# SCH_D69-600V_supply_2024-10-20.net
KiCad netlist of a schematic drawn in EasyEDA
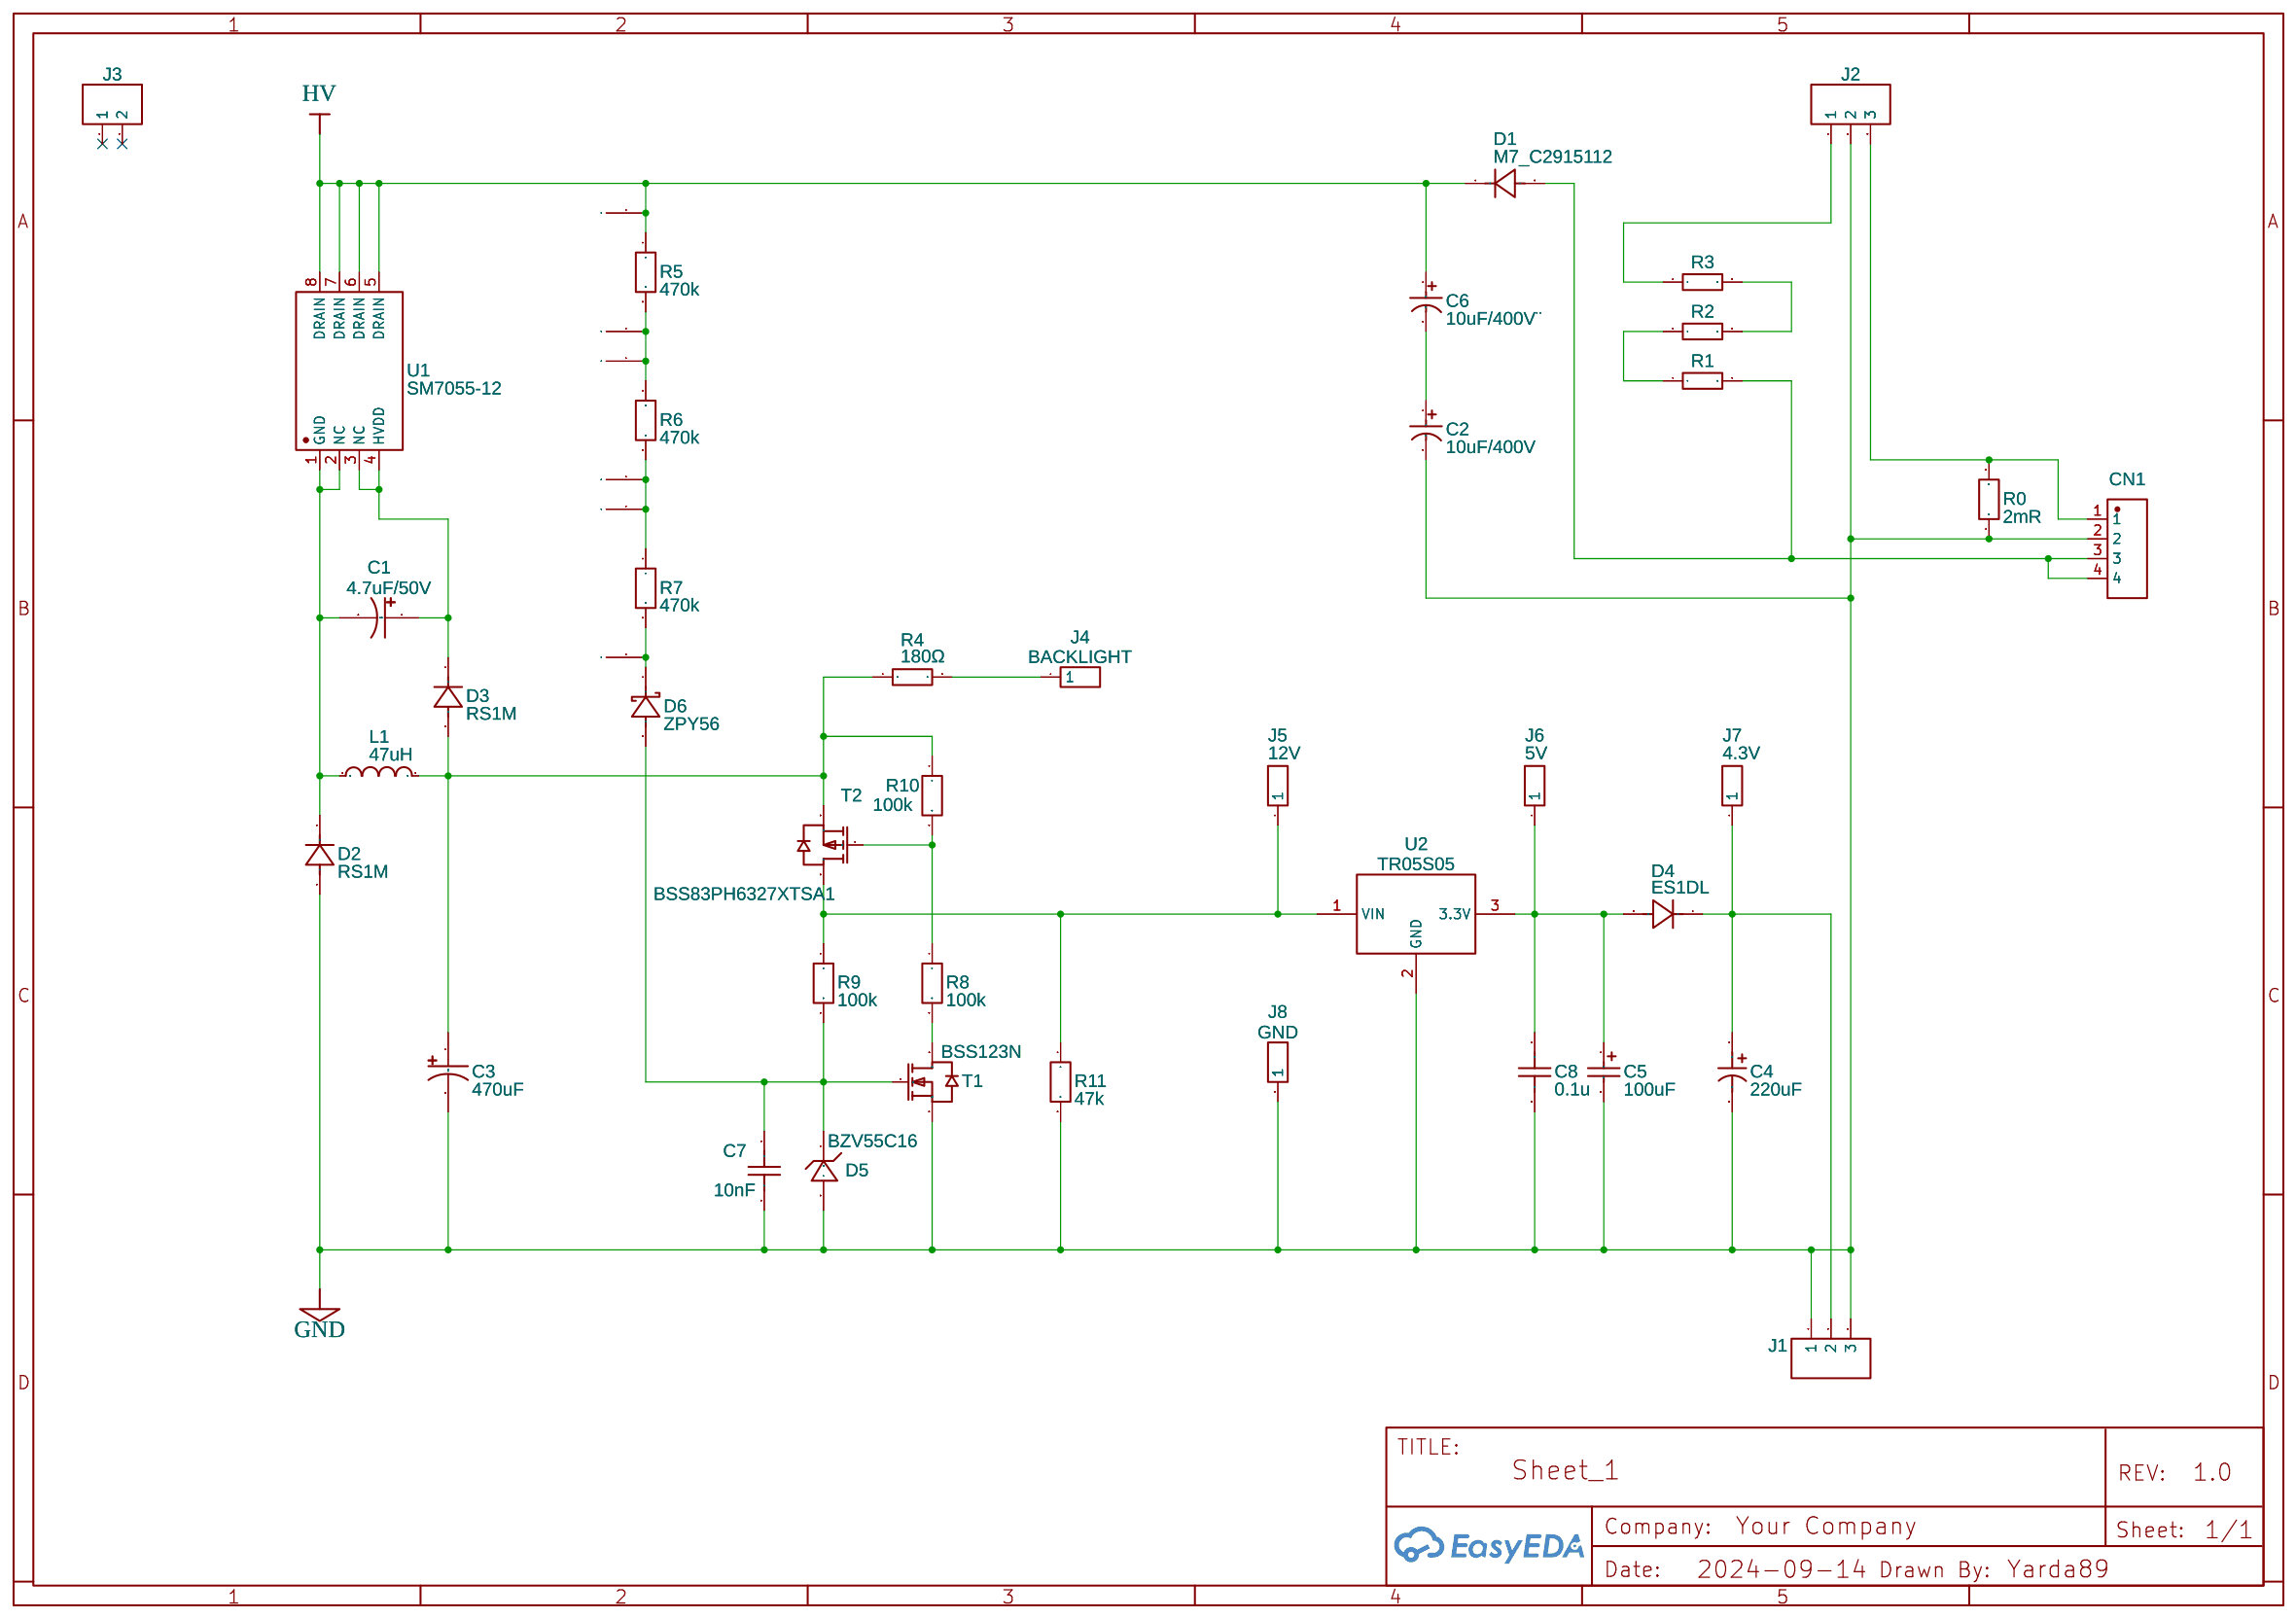
[diagram p0: schematic sheet]

(export (version "E")
  (design (tool "Eeschema 10.0.6"))
  (components
    (comp (ref "C1")
      (value "4.7uF/50V")
      (fields (field (name "Manufacturer Part") "EEUFR1H4R7") (field (name "Manufacturer") "PANASONIC(松下)"))
      (libsource (lib "") (part "EEUFR1H4R7"))
    )
    (comp (ref "C2")
      (value "10uF/400V")
      (fields (field (name "Manufacturer Part") "UCS2G100MPD") (field (name "Manufacturer") "Nichicon(尼吉康)"))
      (libsource (lib "") (part "UCS2G100MPD"))
    )
    (comp (ref "C3")
      (value "470uF")
      (fields (field (name "Manufacturer Part") "EEUFR1E471Y") (field (name "Manufacturer") "PANASONIC(松下)"))
      (libsource (lib "") (part "EEUFR1E471Y"))
    )
    (comp (ref "C4")
      (value "220uF")
      (fields (field (name "Manufacturer Part") "ECA1CM221") (field (name "Manufacturer") "PANASONIC(松下)"))
      (libsource (lib "") (part "ECA1CM221"))
    )
    (comp (ref "C5")
      (value "100uF")
      (fields (field (name "Manufacturer Part") "TAJD107M016RNJ") (field (name "Manufacturer") "Kyocera AVX"))
      (libsource (lib "") (part "TAJD107M016RNJ"))
    )
    (comp (ref "C6")
      (value "10uF/400V¨")
      (fields (field (name "Manufacturer Part") "UCS2G100MPD") (field (name "Manufacturer") "Nichicon(尼吉康)"))
      (libsource (lib "") (part "UCS2G100MPD"))
    )
    (comp (ref "C7")
      (value "10nF")
      (fields
        (field (name "Manufacturer Part") "CC1H103ZA1ED3F4D1100")
        (field (name "Manufacturer") "Dersonic(德尔创)")
      )
      (libsource (lib "") (part "CC1H103ZA1ED3F4D1100"))
    )
    (comp (ref "C8") (value "0.1u") (libsource (lib "") (part "C_0603_US")))
    (comp (ref "CN1")
      (value "MX128-5.0-04P-GN01-CU-Y-A")
      (fields
        (field (name "Manufacturer Part") "MX128-5.0-04P-GN01-Cu-Y-A")
        (field (name "Manufacturer") "MAX(迈旭)")
      )
      (libsource (lib "") (part "MX128-5.0-04P-GN01-CU-Y-A"))
    )
    (comp (ref "D1")
      (value "M7_C2915112")
      (fields (field (name "Manufacturer Part") "M7") (field (name "Manufacturer") "GOODWORK(固得沃克)"))
      (libsource (lib "") (part "M7_C2915112"))
    )
    (comp (ref "D2")
      (value "RS1M")
      (fields (field (name "Manufacturer") "YFSEMI(江苏佑风微)"))
      (libsource (lib "") (part "RS1M"))
    )
    (comp (ref "D3")
      (value "RS1M")
      (fields (field (name "Manufacturer") "YFSEMI(江苏佑风微)"))
      (libsource (lib "") (part "RS1M"))
    )
    (comp (ref "D4")
      (value "ES1DL")
      (fields (field (name "Manufacturer") "CJ(江苏长电/长晶)"))
      (libsource (lib "") (part "ES1DL"))
    )
    (comp (ref "D5")
      (value "BZV55C16")
      (fields (field (name "Manufacturer") "LGE(鲁光)"))
      (libsource (lib "") (part "BZV55C16"))
    )
    (comp (ref "D6") (value "ZPY56") (libsource (lib "") (part "ZPY56")))
    (comp (ref "J1") (value "HDR-M-2.54_1x3") (libsource (lib "") (part "HDR-M-2.54_1x3")))
    (comp (ref "J2") (value "HDR-M-2.54_1x3") (libsource (lib "") (part "HDR-M-2.54_1x3_1")))
    (comp (ref "J3") (value "HDR-M-2.54_1x2") (libsource (lib "") (part "HDR-M-2.54_1x2")))
    (comp (ref "J4") (value "BACKLIGHT") (libsource (lib "") (part "HDR-M-2.54_1x1_1")))
    (comp (ref "J5") (value "12V") (libsource (lib "") (part "HDR-M-2.54_1x1")))
    (comp (ref "J6") (value "5V") (libsource (lib "") (part "HDR-M-2.54_1x1")))
    (comp (ref "J7") (value "4.3V") (libsource (lib "") (part "HDR-M-2.54_1x1")))
    (comp (ref "J8") (value "GND") (libsource (lib "") (part "HDR-M-2.54_1x1")))
    (comp (ref "L1")
      (value "47uH")
      (fields
        (field (name "Manufacturer Part") "SLP0608R-470MTT")
        (field (name "Manufacturer") "Sunltech(韩国顺磁)")
      )
      (libsource (lib "") (part "SLP0608R-470MTT"))
    )
    (comp (ref "R0") (value "2mR") (libsource (lib "") (part "R_1812_EU")))
    (comp (ref "R1")
      (value "510kΩ")
      (fields
        (field (name "Manufacturer Part") "1206W4F5103T5E")
        (field (name "Manufacturer") "UNI-ROYAL(厚声)")
      )
      (libsource (lib "") (part "1206W4F5103T5E"))
    )
    (comp (ref "R2")
      (value "510kΩ")
      (fields
        (field (name "Manufacturer Part") "1206W4F5103T5E")
        (field (name "Manufacturer") "UNI-ROYAL(厚声)")
      )
      (libsource (lib "") (part "1206W4F5103T5E"))
    )
    (comp (ref "R3")
      (value "510kΩ")
      (fields
        (field (name "Manufacturer Part") "1206W4F5103T5E")
        (field (name "Manufacturer") "UNI-ROYAL(厚声)")
      )
      (libsource (lib "") (part "1206W4F5103T5E"))
    )
    (comp (ref "R4")
      (value "180Ω")
      (fields
        (field (name "Manufacturer Part") "1206W4F1800T5E")
        (field (name "Manufacturer") "UNI-ROYAL(厚声)")
      )
      (libsource (lib "") (part "1206W4F1800T5E"))
    )
    (comp (ref "R5") (value "470k") (libsource (lib "") (part "R_1206_EU")))
    (comp (ref "R6") (value "470k") (libsource (lib "") (part "R_1206_EU")))
    (comp (ref "R7") (value "470k") (libsource (lib "") (part "R_1206_EU")))
    (comp (ref "R8") (value "100k") (libsource (lib "") (part "R_0805_EU")))
    (comp (ref "R9") (value "100k") (libsource (lib "") (part "R_0805_EU")))
    (comp (ref "R10") (value "100k") (libsource (lib "") (part "R_0805_EU")))
    (comp (ref "R11") (value "47k") (libsource (lib "") (part "R_AXIAL-0.4_EU")))
    (comp (ref "T1")
      (value "BSS123N")
      (fields (field (name "Manufacturer") "Infineon(英飞凌)"))
      (libsource (lib "") (part "BSS123N"))
    )
    (comp (ref "T2")
      (value "BSS83PH6327XTSA1")
      (fields (field (name "Manufacturer") "Infineon Technologies"))
      (libsource (lib "") (part "BSS83PH6327XTSA1"))
    )
    (comp (ref "U1")
      (value "SM7055-12")
      (fields (field (name "Manufacturer") "明微"))
      (libsource (lib "") (part "SM7055-12"))
    )
    (comp (ref "U2")
      (value "TR05S05")
      (fields (field (name "Manufacturer Part") "1470-2257-5-ND"))
      (libsource (lib "") (part "TR05S3V3"))
    )
    (comp (ref "U3")
      (value "KX_PAD_SMD_3X1.5MM COPY COPY")
      (libsource (lib "") (part "KX_PAD_SMD_3X1.5MM COPY COPY"))
    )
    (comp (ref "U4")
      (value "KX_PAD_SMD_3X1.5MM COPY COPY")
      (libsource (lib "") (part "KX_PAD_SMD_3X1.5MM COPY COPY"))
    )
    (comp (ref "U5")
      (value "KX_PAD_SMD_3X1.5MM COPY COPY")
      (libsource (lib "") (part "KX_PAD_SMD_3X1.5MM COPY COPY"))
    )
    (comp (ref "U6")
      (value "KX_PAD_SMD_3X1.5MM COPY COPY")
      (libsource (lib "") (part "KX_PAD_SMD_3X1.5MM COPY COPY"))
    )
    (comp (ref "U7")
      (value "KX_PAD_SMD_3X1.5MM COPY COPY")
      (libsource (lib "") (part "KX_PAD_SMD_3X1.5MM COPY COPY"))
    )
    (comp (ref "U8")
      (value "KX_PAD_SMD_3X1.5MM COPY COPY")
      (libsource (lib "") (part "KX_PAD_SMD_3X1.5MM COPY COPY"))
    )
  )
  (nets
    (net (code "1") (name "GND") (class "Default")
      (node (ref "C2") (pin "2") (pinfunction "2_2") (pintype "input"))
      (node (ref "C3") (pin "2") (pinfunction "2_2") (pintype "unspecified"))
      (node (ref "C4") (pin "2") (pinfunction "2_2") (pintype "input"))
      (node (ref "C5") (pin "2") (pinfunction "2_2") (pintype "input"))
      (node (ref "C7") (pin "2") (pinfunction "2_2") (pintype "unspecified"))
      (node (ref "C8") (pin "2") (pinfunction "2_2") (pintype "unspecified"))
      (node (ref "CN1") (pin "2") (pinfunction "2_2") (pintype "unspecified"))
      (node (ref "D2") (pin "2") (pinfunction "A_2") (pintype "unspecified"))
      (node (ref "D5") (pin "2") (pinfunction "A_2") (pintype "unspecified"))
      (node (ref "J1") (pin "1") (pinfunction "1_1") (pintype "input"))
      (node (ref "J1") (pin "3") (pinfunction "3_3") (pintype "input"))
      (node (ref "J2") (pin "2") (pinfunction "2_2") (pintype "input"))
      (node (ref "J8") (pin "1") (pinfunction "1_1") (pintype "input"))
      (node (ref "R0") (pin "1") (pinfunction "1_1") (pintype "unspecified"))
      (node (ref "R11") (pin "2") (pinfunction "2_2") (pintype "unspecified"))
      (node (ref "T1") (pin "2") (pinfunction "S_2") (pintype "unspecified"))
      (node (ref "U2") (pin "2") (pinfunction "GND_2") (pintype "unspecified"))
    )
    (net (code "2") (name "HV") (class "Default")
      (node (ref "C6") (pin "1") (pinfunction "1_1") (pintype "input"))
      (node (ref "D1") (pin "1") (pinfunction "K_1") (pintype "unspecified"))
      (node (ref "R5") (pin "1") (pinfunction "1_1") (pintype "unspecified"))
      (node (ref "U1") (pin "5") (pinfunction "DRAIN_5") (pintype "unspecified"))
      (node (ref "U1") (pin "6") (pinfunction "DRAIN_6") (pintype "unspecified"))
      (node (ref "U1") (pin "7") (pinfunction "DRAIN_7") (pintype "unspecified"))
      (node (ref "U1") (pin "8") (pinfunction "DRAIN_8") (pintype "unspecified"))
      (node (ref "U3") (pin "1") (pinfunction "1_1") (pintype "unspecified"))
    )
    (net (code "3") (name "Net-(C2-Pad1)") (class "Default")
      (node (ref "C2") (pin "1") (pinfunction "1_1") (pintype "input"))
      (node (ref "C6") (pin "2") (pinfunction "2_2") (pintype "input"))
    )
    (net (code "4") (name "Net-(CN1-Pad1)") (class "Default")
      (node (ref "CN1") (pin "1") (pinfunction "1_1") (pintype "unspecified"))
      (node (ref "J2") (pin "3") (pinfunction "3_3") (pintype "input"))
      (node (ref "R0") (pin "2") (pinfunction "2_2") (pintype "unspecified"))
    )
    (net (code "5") (name "Net-(D1-A)") (class "Default")
      (node (ref "CN1") (pin "3") (pinfunction "3_3") (pintype "unspecified"))
      (node (ref "CN1") (pin "4") (pinfunction "4_4") (pintype "unspecified"))
      (node (ref "D1") (pin "2") (pinfunction "A_2") (pintype "unspecified"))
      (node (ref "R1") (pin "2") (pinfunction "2_2") (pintype "input"))
    )
    (net (code "6") (name "Net-(D2-K)") (class "Default")
      (node (ref "C1") (pin "2") (pinfunction "2_2") (pintype "unspecified"))
      (node (ref "D2") (pin "1") (pinfunction "K_1") (pintype "unspecified"))
      (node (ref "L1") (pin "1") (pinfunction "1_1") (pintype "unspecified"))
      (node (ref "U1") (pin "1") (pinfunction "GND_1") (pintype "unspecified"))
      (node (ref "U1") (pin "2") (pinfunction "NC_2") (pintype "unspecified"))
    )
    (net (code "7") (name "Net-(D3-A)") (class "Default")
      (node (ref "C3") (pin "1") (pinfunction "1_1") (pintype "unspecified"))
      (node (ref "D3") (pin "2") (pinfunction "A_2") (pintype "unspecified"))
      (node (ref "L1") (pin "2") (pinfunction "2_2") (pintype "unspecified"))
      (node (ref "R10") (pin "1") (pinfunction "1_1") (pintype "unspecified"))
      (node (ref "R4") (pin "1") (pinfunction "1_1") (pintype "input"))
      (node (ref "T2") (pin "2") (pinfunction "S_2") (pintype "unspecified"))
    )
    (net (code "8") (name "Net-(D3-K)") (class "Default")
      (node (ref "C1") (pin "1") (pinfunction "1_1") (pintype "unspecified"))
      (node (ref "D3") (pin "1") (pinfunction "K_1") (pintype "unspecified"))
      (node (ref "U1") (pin "3") (pinfunction "NC_3") (pintype "unspecified"))
      (node (ref "U1") (pin "4") (pinfunction "HVDD_4") (pintype "unspecified"))
    )
    (net (code "9") (name "Net-(D4-A)") (class "Default")
      (node (ref "C5") (pin "1") (pinfunction "1_1") (pintype "input"))
      (node (ref "C8") (pin "1") (pinfunction "1_1") (pintype "unspecified"))
      (node (ref "D4") (pin "2") (pinfunction "A_2") (pintype "unspecified"))
      (node (ref "J6") (pin "1") (pinfunction "1_1") (pintype "input"))
      (node (ref "U2") (pin "3") (pinfunction "3.3V_3") (pintype "unspecified"))
    )
    (net (code "10") (name "Net-(D4-K)") (class "Default")
      (node (ref "C4") (pin "1") (pinfunction "1_1") (pintype "input"))
      (node (ref "D4") (pin "1") (pinfunction "K_1") (pintype "unspecified"))
      (node (ref "J1") (pin "2") (pinfunction "2_2") (pintype "input"))
      (node (ref "J7") (pin "1") (pinfunction "1_1") (pintype "input"))
    )
    (net (code "11") (name "Net-(D5-C)") (class "Default")
      (node (ref "C7") (pin "1") (pinfunction "1_1") (pintype "unspecified"))
      (node (ref "D5") (pin "1") (pinfunction "C_1") (pintype "unspecified"))
      (node (ref "D6") (pin "2") (pinfunction "A_2") (pintype "unspecified"))
      (node (ref "R9") (pin "2") (pinfunction "2_2") (pintype "unspecified"))
      (node (ref "T1") (pin "1") (pinfunction "G_1") (pintype "unspecified"))
    )
    (net (code "12") (name "Net-(D6-K)") (class "Default")
      (node (ref "D6") (pin "1") (pinfunction "K_1") (pintype "unspecified"))
      (node (ref "R7") (pin "2") (pinfunction "2_2") (pintype "unspecified"))
      (node (ref "U6") (pin "1") (pinfunction "1_1") (pintype "unspecified"))
    )
    (net (code "13") (name "Net-(J2-Pad1)") (class "Default")
      (node (ref "J2") (pin "1") (pinfunction "1_1") (pintype "input"))
      (node (ref "R3") (pin "1") (pinfunction "1_1") (pintype "input"))
    )
    (net (code "14") (name "Net-(J4-Pad1)") (class "Default")
      (node (ref "J4") (pin "1") (pinfunction "1_1") (pintype "input"))
      (node (ref "R4") (pin "2") (pinfunction "2_2") (pintype "input"))
    )
    (net (code "15") (name "Net-(R1-Pad1)") (class "Default")
      (node (ref "R1") (pin "1") (pinfunction "1_1") (pintype "input"))
      (node (ref "R2") (pin "1") (pinfunction "1_1") (pintype "input"))
    )
    (net (code "16") (name "Net-(R2-Pad2)") (class "Default")
      (node (ref "R2") (pin "2") (pinfunction "2_2") (pintype "input"))
      (node (ref "R3") (pin "2") (pinfunction "2_2") (pintype "input"))
    )
    (net (code "17") (name "Net-(R5-Pad2)") (class "Default")
      (node (ref "R5") (pin "2") (pinfunction "2_2") (pintype "unspecified"))
      (node (ref "R6") (pin "1") (pinfunction "1_1") (pintype "unspecified"))
      (node (ref "U4") (pin "1") (pinfunction "1_1") (pintype "unspecified"))
      (node (ref "U8") (pin "1") (pinfunction "1_1") (pintype "unspecified"))
    )
    (net (code "18") (name "Net-(R6-Pad2)") (class "Default")
      (node (ref "R6") (pin "2") (pinfunction "2_2") (pintype "unspecified"))
      (node (ref "R7") (pin "1") (pinfunction "1_1") (pintype "unspecified"))
      (node (ref "U5") (pin "1") (pinfunction "1_1") (pintype "unspecified"))
      (node (ref "U7") (pin "1") (pinfunction "1_1") (pintype "unspecified"))
    )
    (net (code "19") (name "Net-(T1-D)") (class "Default")
      (node (ref "R8") (pin "2") (pinfunction "2_2") (pintype "unspecified"))
      (node (ref "T1") (pin "3") (pinfunction "D_3") (pintype "unspecified"))
    )
    (net (code "20") (name "Net-(T2-D)") (class "Default")
      (node (ref "J5") (pin "1") (pinfunction "1_1") (pintype "input"))
      (node (ref "R11") (pin "1") (pinfunction "1_1") (pintype "unspecified"))
      (node (ref "R9") (pin "1") (pinfunction "1_1") (pintype "unspecified"))
      (node (ref "T2") (pin "3") (pinfunction "D_3") (pintype "unspecified"))
      (node (ref "U2") (pin "1") (pinfunction "VIN_1") (pintype "unspecified"))
    )
    (net (code "21") (name "Net-(T2-G)") (class "Default")
      (node (ref "R10") (pin "2") (pinfunction "2_2") (pintype "unspecified"))
      (node (ref "R8") (pin "1") (pinfunction "1_1") (pintype "unspecified"))
      (node (ref "T2") (pin "1") (pinfunction "G_1") (pintype "unspecified"))
    )
    (net (code "22") (name "unconnected-(J3-Pad1)") (class "Default")
      (node (ref "J3") (pin "1") (pinfunction "1_1") (pintype "unspecified+no_connect"))
    )
    (net (code "23") (name "unconnected-(J3-Pad2)") (class "Default")
      (node (ref "J3") (pin "2") (pinfunction "2_2") (pintype "unspecified+no_connect"))
    )
  )
)
